# n2k-breakout-3_0-ISO.net
KiCad netlist of a schematic drawn in EAGLE
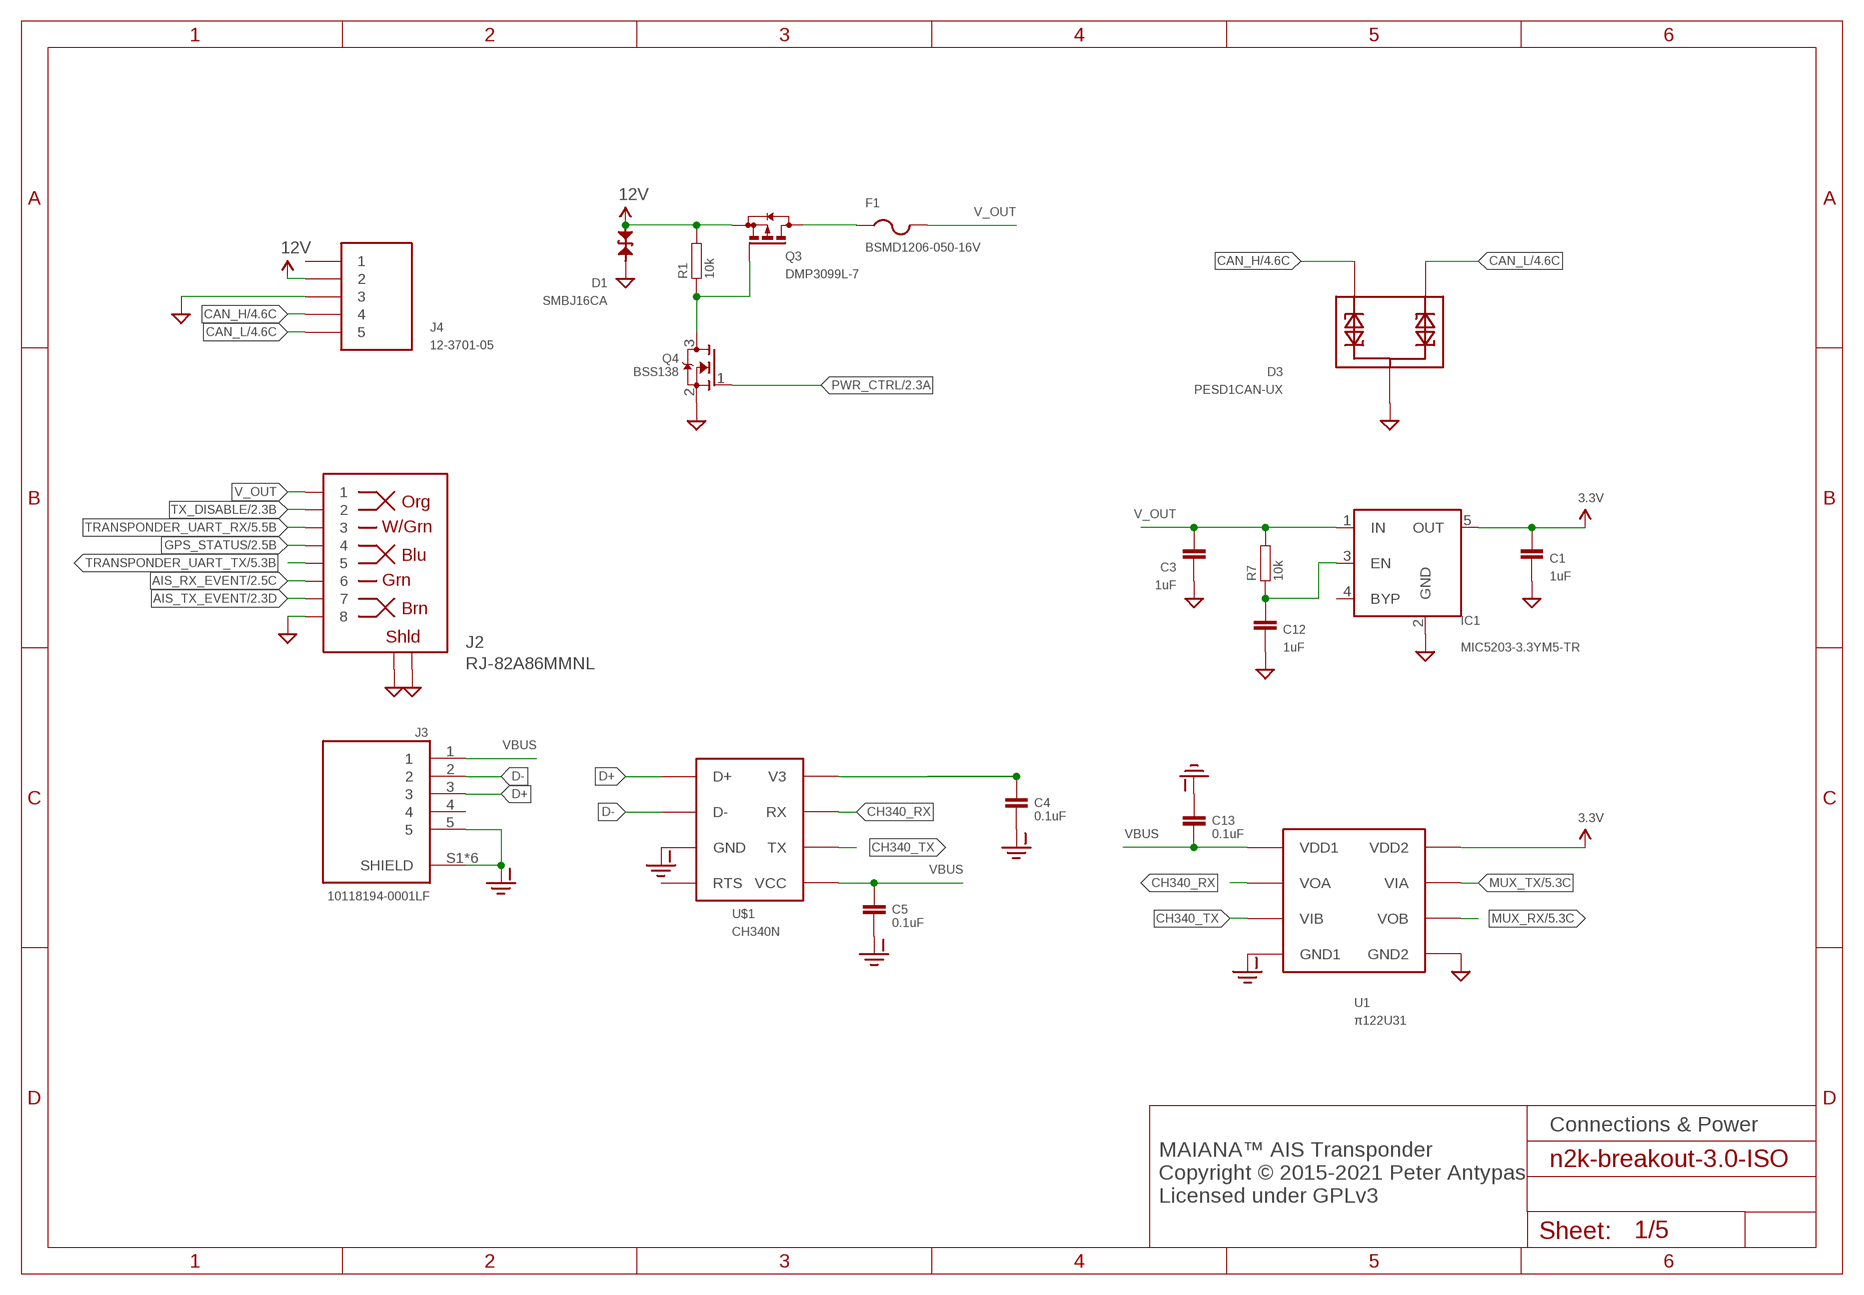
[diagram p0: schematic, sheet 1]
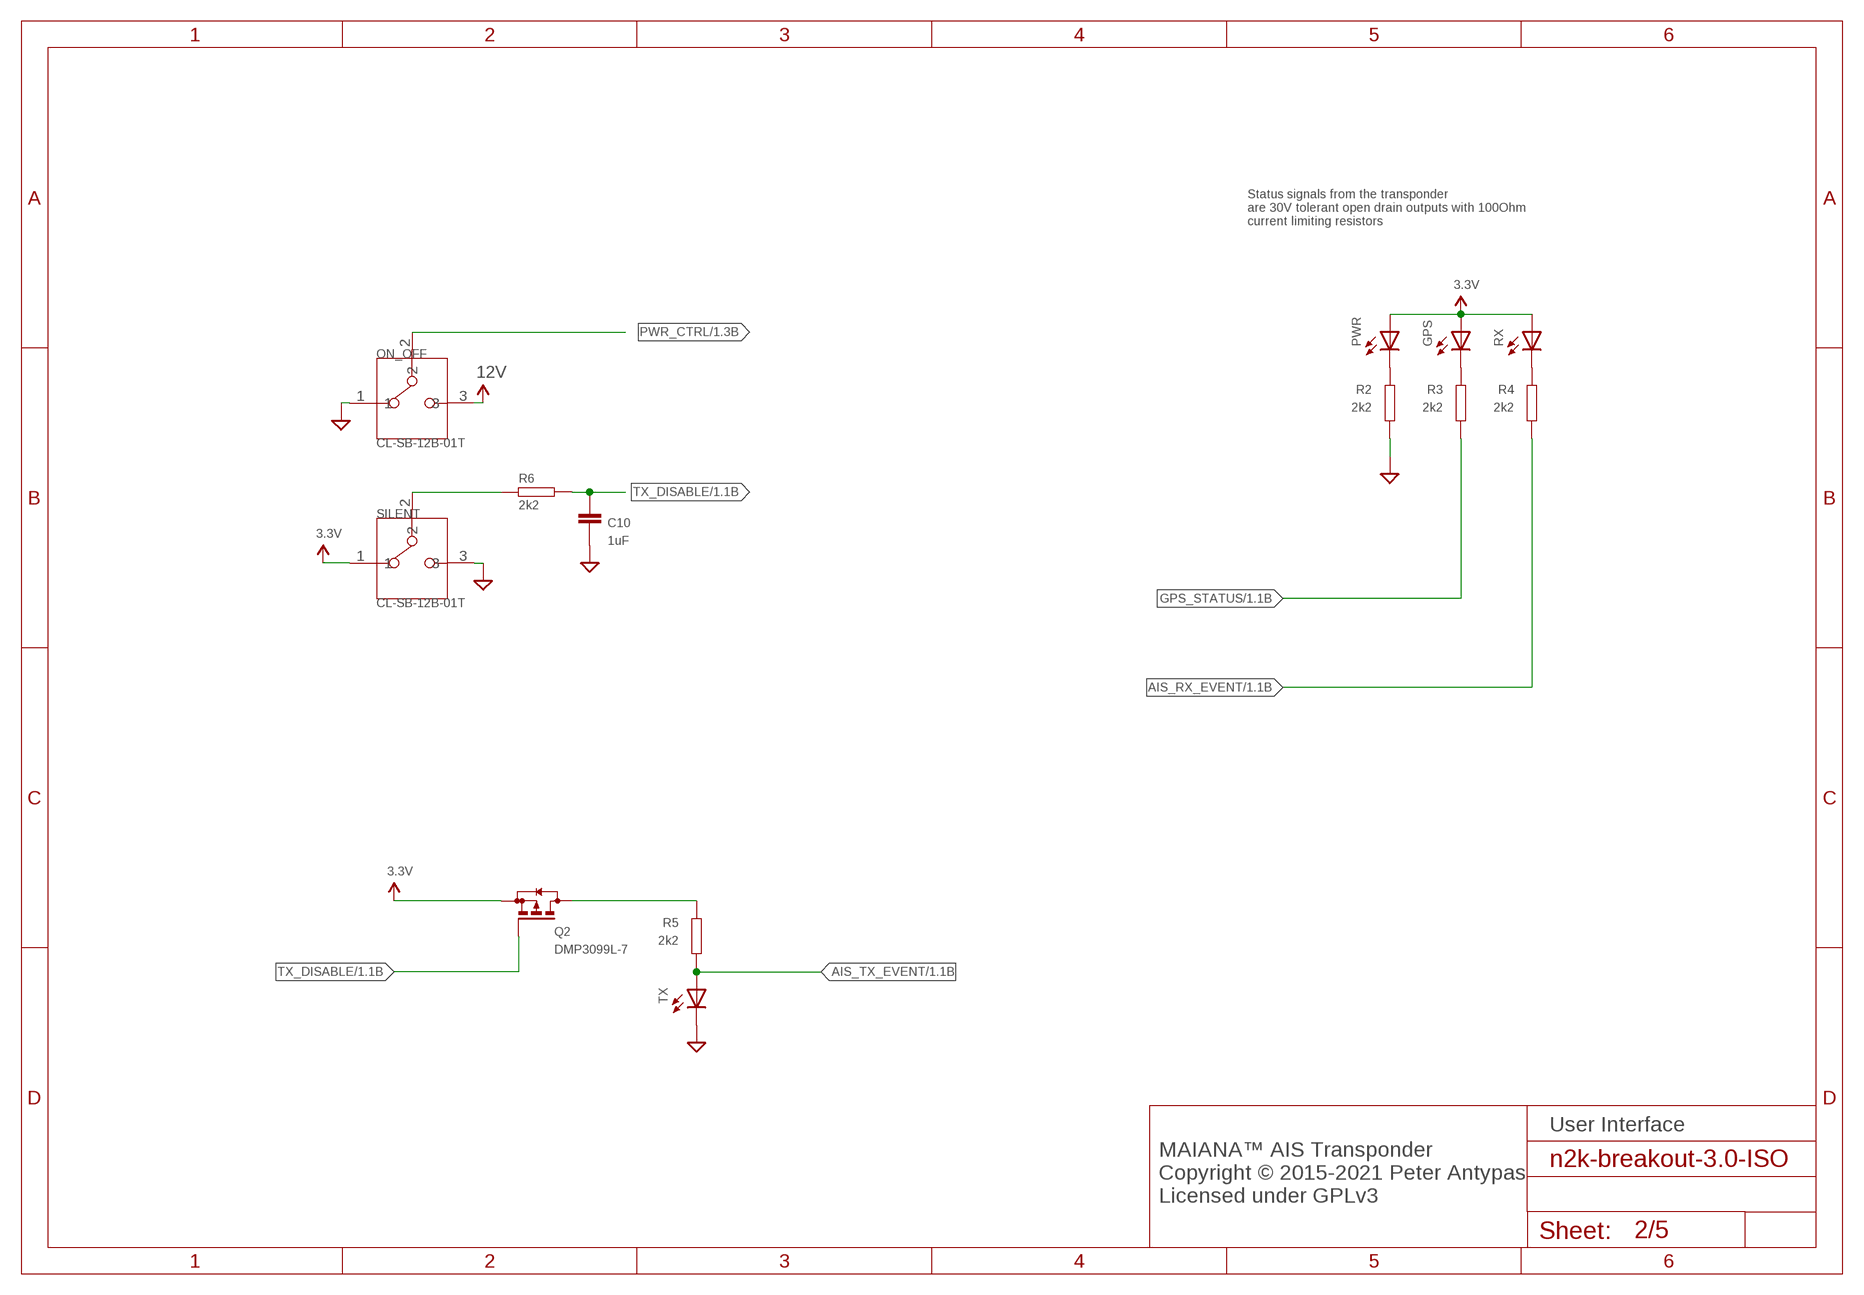
[diagram p1: schematic, sheet 2]
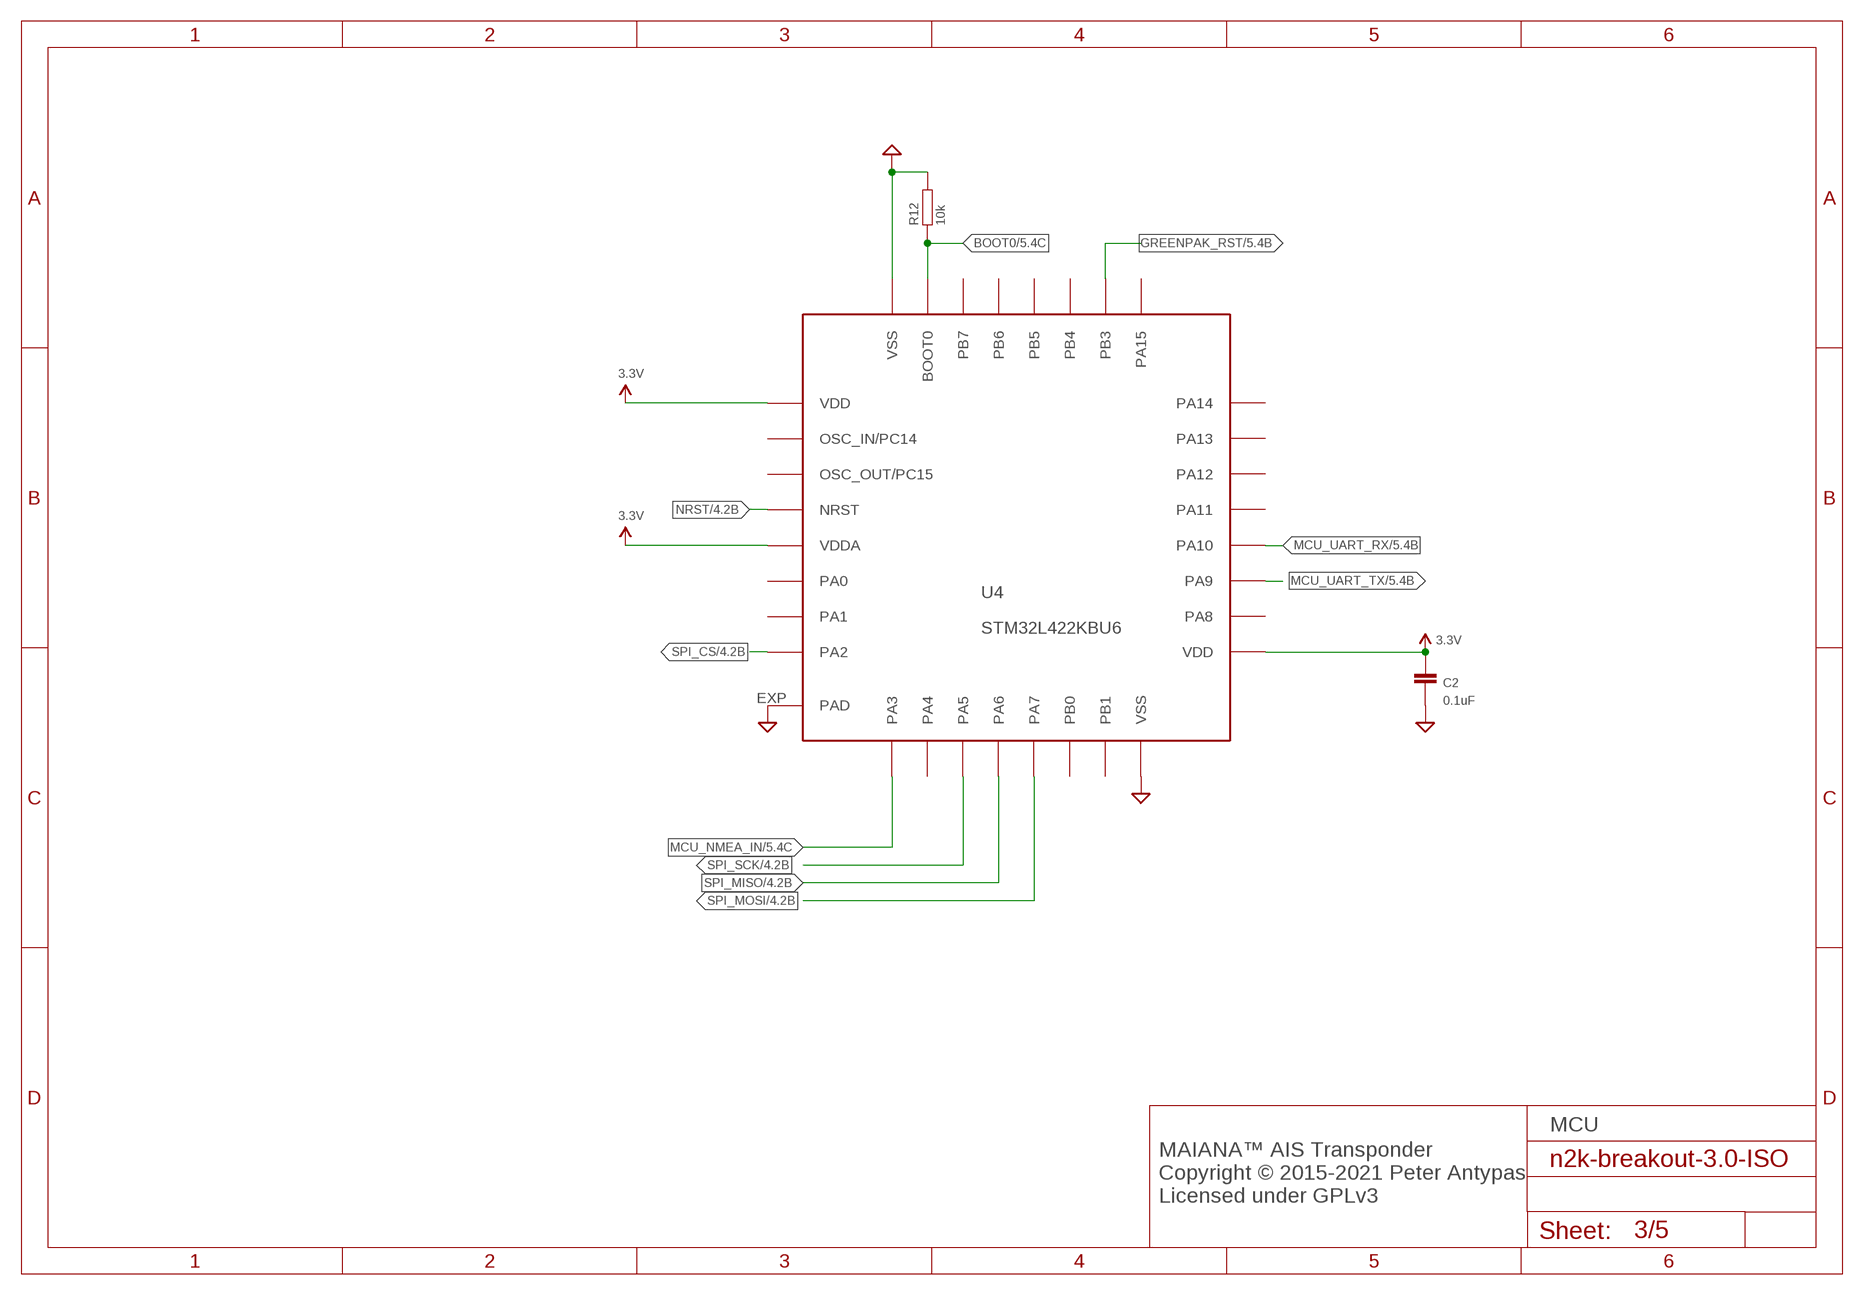
[diagram p2: schematic, sheet 3]
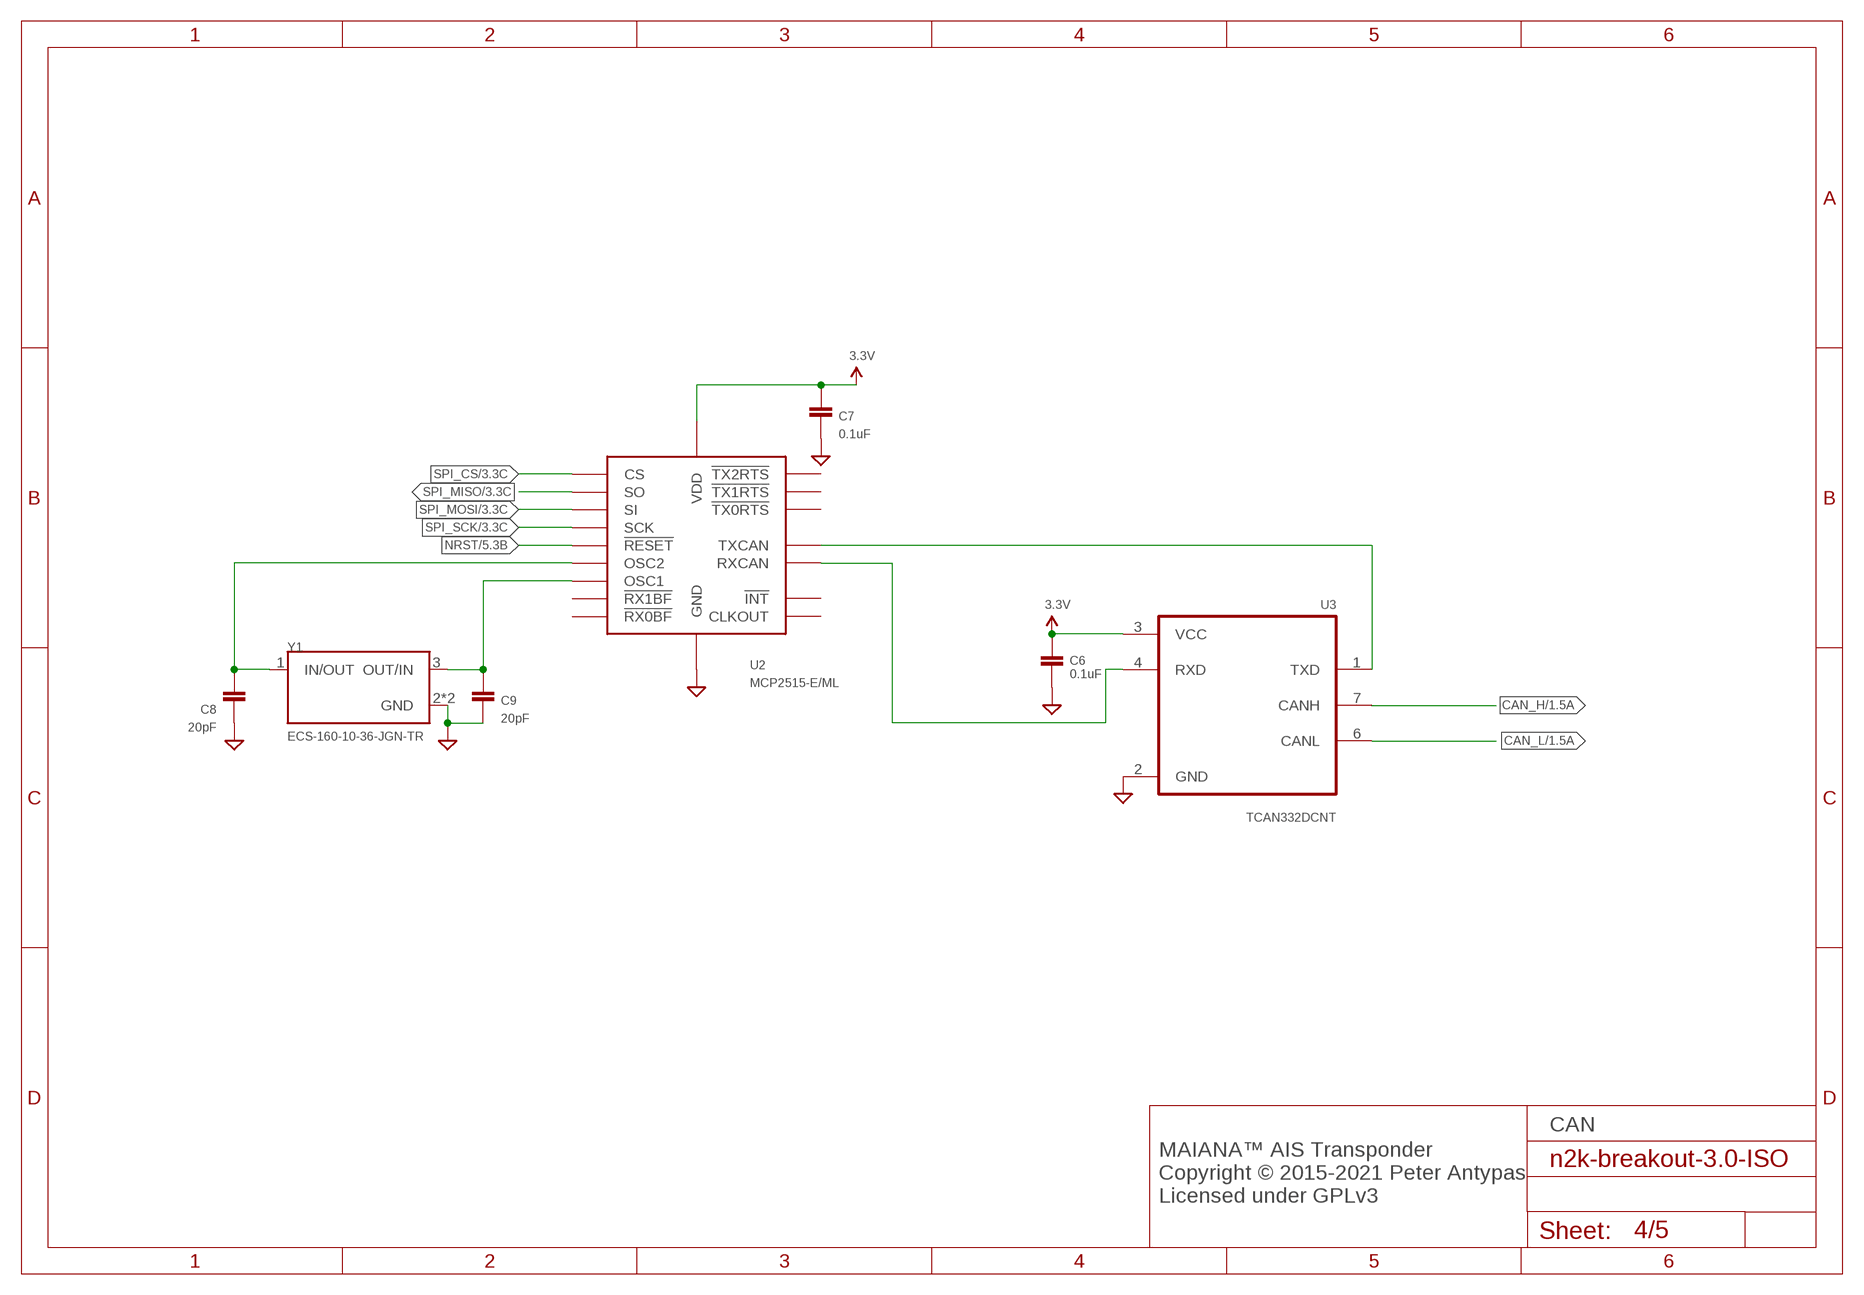
[diagram p3: schematic, sheet 4]
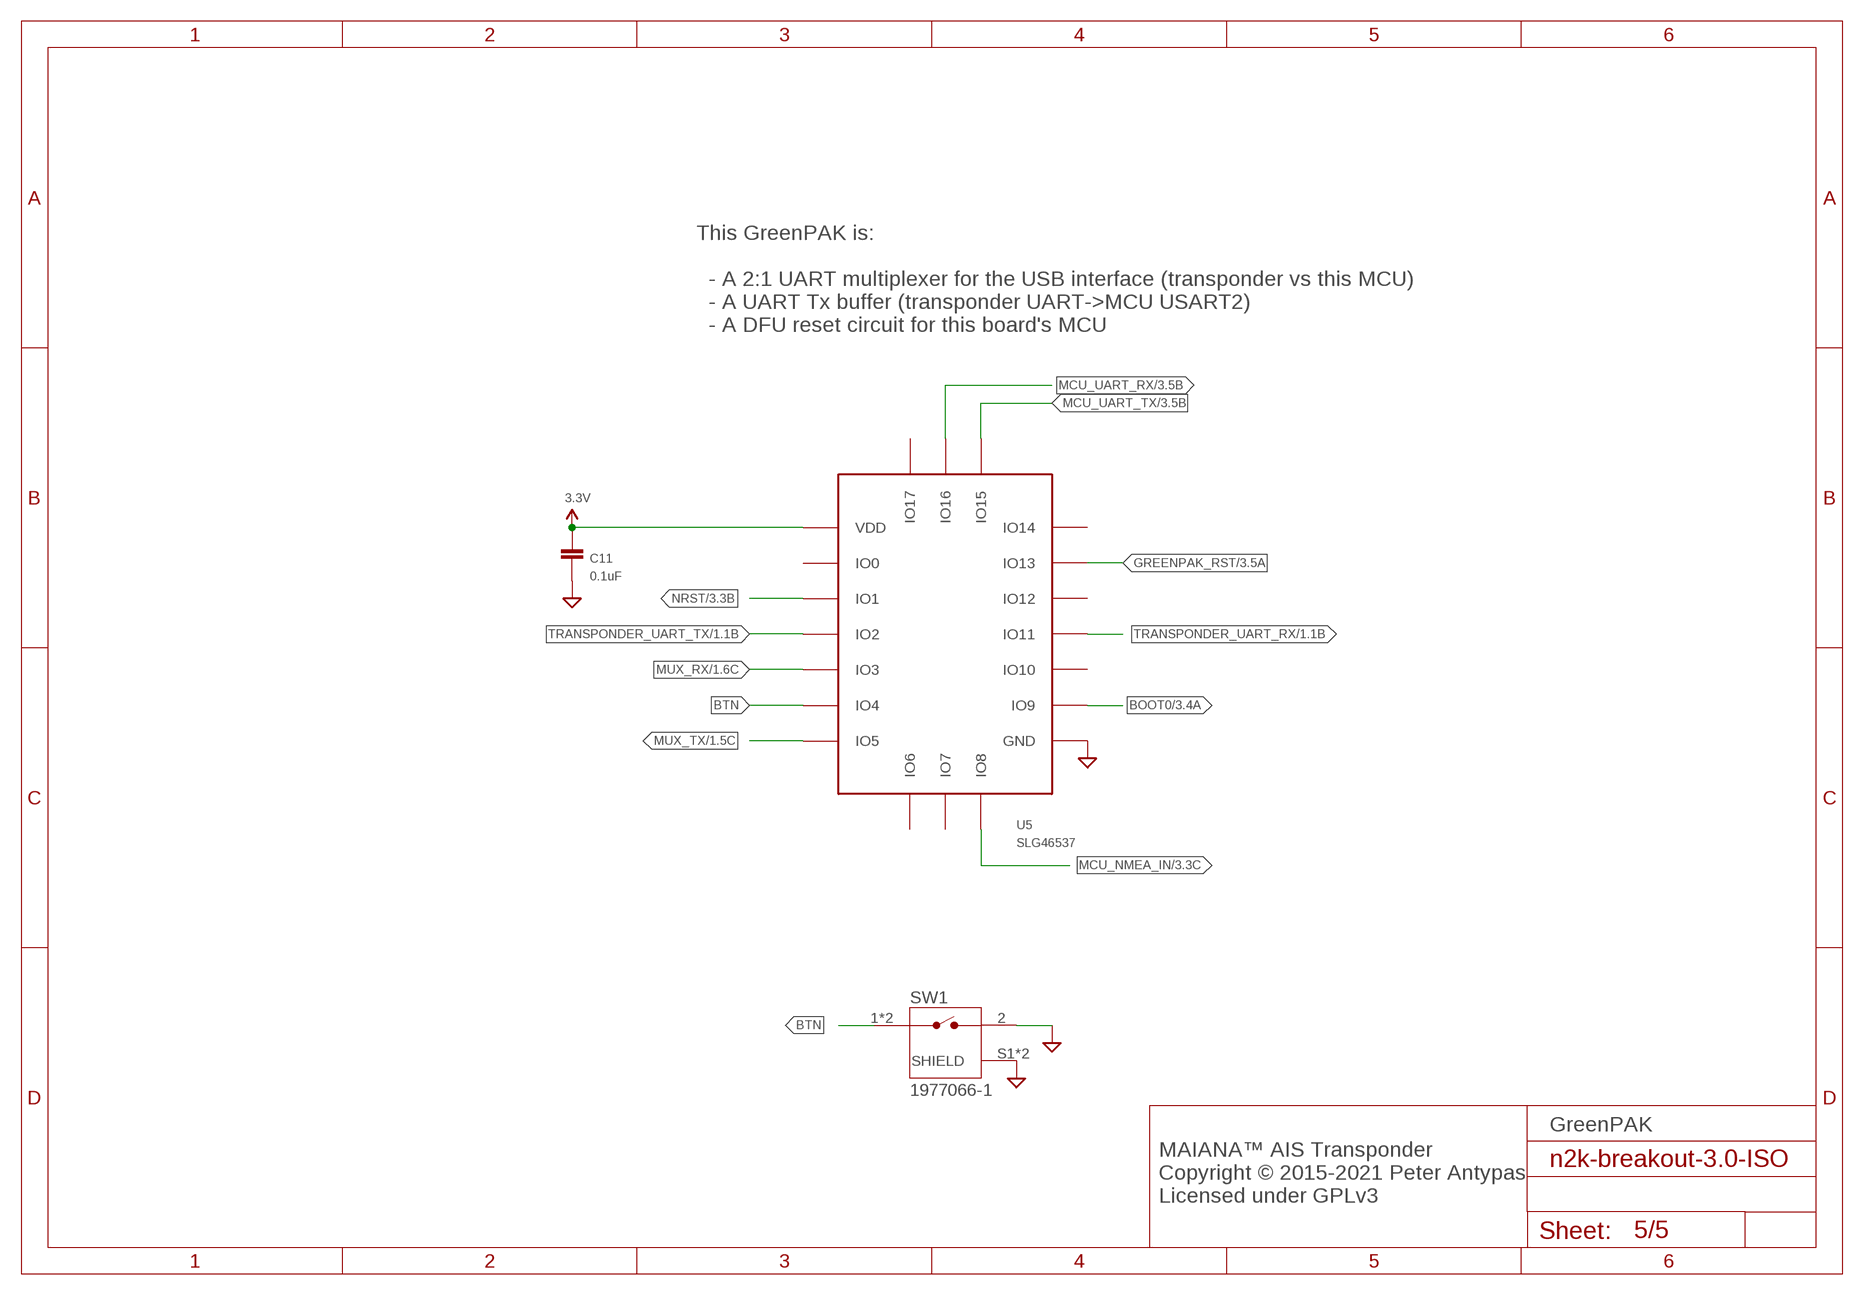
[diagram p4: schematic, sheet 5]

(export (version "E")
  (design (tool "Eeschema 10.0.6"))
  (components
    (comp (ref "C10")
      (value "1uF")
      (footprint "eagle-import:0603")
      (libsource (lib "eagle-import") (part "CAPACITOR0603"))
    )
    (comp (ref "GPS")
      (value "LEDCHIPLED_1206")
      (footprint "eagle-import:CHIPLED_1206")
      (fields (field (name "PARTNO") "TJ-S3216CL9T5ALC2G-A5"))
      (libsource (lib "eagle-import") (part "LEDCHIPLED_1206"))
    )
    (comp (ref "ON_OFF")
      (value "CL-SB-12B-01T")
      (footprint "eagle-import:CL-SB-12B")
      (fields (field (name "MF") "Nidec Copal"))
      (libsource (lib "eagle-import") (part "CL-SB-12B-01T"))
    )
    (comp (ref "PWR")
      (value "LEDCHIPLED_1206")
      (footprint "eagle-import:CHIPLED_1206")
      (fields (field (name "PARTNO") "TJ-S3216CL9T5ALC2G-A5"))
      (libsource (lib "eagle-import") (part "LEDCHIPLED_1206"))
    )
    (comp (ref "Q2")
      (value "DMP3099L-7")
      (footprint "eagle-import:SOT23")
      (libsource (lib "eagle-import") (part "BSS84"))
    )
    (comp (ref "R2")
      (value "2k2")
      (footprint "eagle-import:0603")
      (libsource (lib "eagle-import") (part "RESISTOR0603"))
    )
    (comp (ref "R3")
      (value "2k2")
      (footprint "eagle-import:0603")
      (libsource (lib "eagle-import") (part "RESISTOR0603"))
    )
    (comp (ref "R4")
      (value "2k2")
      (footprint "eagle-import:0603")
      (libsource (lib "eagle-import") (part "RESISTOR0603"))
    )
    (comp (ref "R5")
      (value "2k2")
      (footprint "eagle-import:0603")
      (libsource (lib "eagle-import") (part "RESISTOR0603"))
    )
    (comp (ref "R6")
      (value "2k2")
      (footprint "eagle-import:0603")
      (libsource (lib "eagle-import") (part "RESISTOR0603"))
    )
    (comp (ref "RX")
      (value "LEDCHIPLED_1206")
      (footprint "eagle-import:CHIPLED_1206")
      (fields (field (name "PARTNO") "TJ-S3216CL9T5ALC2G-A5"))
      (libsource (lib "eagle-import") (part "LEDCHIPLED_1206"))
    )
    (comp (ref "SILENT")
      (value "CL-SB-12B-01T")
      (footprint "eagle-import:CL-SB-12B")
      (fields (field (name "MF") "Nidec Copal"))
      (libsource (lib "eagle-import") (part "CL-SB-12B-01T"))
    )
    (comp (ref "TX")
      (value "LEDCHIPLED_1206")
      (footprint "eagle-import:CHIPLED_1206")
      (fields (field (name "PARTNO") "TJ-S3216CL9T5ALC2G-A5"))
      (libsource (lib "eagle-import") (part "LEDCHIPLED_1206"))
    )
    (comp (ref "C2")
      (value "0.1uF")
      (footprint "eagle-import:0603")
      (libsource (lib "eagle-import") (part "CAPACITOR0603"))
    )
    (comp (ref "R12")
      (value "10k")
      (footprint "eagle-import:0603")
      (libsource (lib "eagle-import") (part "RESISTOR0603"))
    )
    (comp (ref "U4")
      (value "STM32L422KBU6")
      (footprint "eagle-import:QFN32")
      (libsource (lib "eagle-import") (part "STM32L432KXXX"))
    )
    (comp (ref "C6")
      (value "0.1uF")
      (footprint "eagle-import:0603")
      (libsource (lib "eagle-import") (part "CAPACITOR0603"))
    )
    (comp (ref "C7")
      (value "0.1uF")
      (footprint "eagle-import:0603")
      (libsource (lib "eagle-import") (part "CAPACITOR0603"))
    )
    (comp (ref "C8")
      (value "20pF")
      (footprint "eagle-import:0603")
      (libsource (lib "eagle-import") (part "CAPACITOR0603"))
    )
    (comp (ref "C9")
      (value "20pF")
      (footprint "eagle-import:0603")
      (libsource (lib "eagle-import") (part "CAPACITOR0603"))
    )
    (comp (ref "U2")
      (value "MCP2515-E/ML")
      (footprint "eagle-import:QFN20-4X4")
      (libsource (lib "eagle-import") (part "MCP2515-QFN20"))
    )
    (comp (ref "U3")
      (value "TCAN332DCNT")
      (footprint "eagle-import:SOT65P280X145-8N")
      (fields (field (name "MF") "Texas Instruments") (field (name "MP") "TCAN332GDCNR"))
      (libsource (lib "eagle-import") (part "TCAN332GDCNR"))
    )
    (comp (ref "Y1")
      (value "ECS-160-10-36-JGN-TR")
      (footprint "eagle-import:XTAL_ECS-160-10-36-JGN-TR")
      (fields (field (name "MF") "ECS Inc.") (field (name "MP") "ECS-300-8-36CKM-TR"))
      (libsource (lib "eagle-import") (part "ECS-300-8-36CKM-TR"))
    )
    (comp (ref "C11")
      (value "0.1uF")
      (footprint "eagle-import:0603")
      (libsource (lib "eagle-import") (part "CAPACITOR0603"))
    )
    (comp (ref "SW1")
      (value "1977066-1")
      (footprint "eagle-import:TE_1977066-1")
      (fields (field (name "MF") "TE Connectivity"))
      (libsource (lib "eagle-import") (part "1977066-1"))
    )
    (comp (ref "U5")
      (value "SLG46537")
      (footprint "eagle-import:STQFN20L")
      (libsource (lib "eagle-import") (part "SLG46537"))
    )
    (comp (ref "C1")
      (value "1uF")
      (footprint "eagle-import:0603")
      (libsource (lib "eagle-import") (part "CAPACITOR0603"))
    )
    (comp (ref "C3")
      (value "1uF")
      (footprint "eagle-import:0603")
      (libsource (lib "eagle-import") (part "CAPACITOR0603"))
    )
    (comp (ref "C4")
      (value "0.1uF")
      (footprint "eagle-import:0603")
      (libsource (lib "eagle-import") (part "CAPACITOR0603"))
    )
    (comp (ref "C5")
      (value "0.1uF")
      (footprint "eagle-import:0603")
      (libsource (lib "eagle-import") (part "CAPACITOR0603"))
    )
    (comp (ref "C12")
      (value "1uF")
      (footprint "eagle-import:0603")
      (libsource (lib "eagle-import") (part "CAPACITOR0603"))
    )
    (comp (ref "C13")
      (value "0.1uF")
      (footprint "eagle-import:0603")
      (libsource (lib "eagle-import") (part "CAPACITOR0603"))
    )
    (comp (ref "D1")
      (value "SMBJ16CA")
      (footprint "eagle-import:SMB-BIDIR")
      (libsource (lib "eagle-import") (part "DIODE-TVS-BIDIRSMB"))
    )
    (comp (ref "D3")
      (value "PESD1CAN-UX")
      (footprint "eagle-import:SOT65P210X110-3N")
      (libsource (lib "eagle-import") (part "PESD1CAN-UX"))
    )
    (comp (ref "F1")
      (value "BSMD1206-050-16V")
      (footprint "eagle-import:R1206")
      (libsource (lib "eagle-import") (part "PTCFUSE-1206"))
    )
    (comp (ref "IC1")
      (value "MIC5203-3.3YM5-TR")
      (footprint "eagle-import:SOT23-5")
      (libsource (lib "eagle-import") (part "MIC5219XX"))
    )
    (comp (ref "J2")
      (value "RJ-82A86MMNL")
      (footprint "eagle-import:RJ-82A86MMNL")
      (libsource (lib "eagle-import") (part "RJ-82A86MMNL"))
    )
    (comp (ref "J3")
      (value "10118194-0001LF")
      (footprint "eagle-import:AMPHENOL_10118194-0001LF")
      (fields (field (name "MF") "Amphenol ICC (FCI)"))
      (libsource (lib "eagle-import") (part "10118194-0001LF"))
    )
    (comp (ref "J4")
      (value "12-3701-05")
      (footprint "eagle-import:MICRO_C_5PIN")
      (libsource (lib "eagle-import") (part "12-3701-05"))
    )
    (comp (ref "Q3")
      (value "DMP3099L-7")
      (footprint "eagle-import:SOT23")
      (libsource (lib "eagle-import") (part "BSS84"))
    )
    (comp (ref "Q4")
      (value "BSS138")
      (footprint "eagle-import:SOT23")
      (libsource (lib "eagle-import") (part "MOSFET-NREFLOW"))
    )
    (comp (ref "R1")
      (value "10k")
      (footprint "eagle-import:0603")
      (libsource (lib "eagle-import") (part "RESISTOR0603"))
    )
    (comp (ref "R7")
      (value "10k")
      (footprint "eagle-import:0603")
      (libsource (lib "eagle-import") (part "RESISTOR0603"))
    )
    (comp (ref "U$1")
      (value "CH340N")
      (footprint "eagle-import:SOIC-8")
      (libsource (lib "eagle-import") (part "CH330N"))
    )
    (comp (ref "U1")
      (value "π122U31")
      (footprint "eagle-import:SOIC8")
      (libsource (lib "eagle-import") (part "PI122U3X"))
    )
  )
  (nets
    (net (code "1") (name "3.3V") (class "Default")
      (node (ref "C1") (pin "P$1") (pinfunction "1_P$1") (pintype "passive"))
      (node (ref "C11") (pin "P$1") (pinfunction "1_P$1") (pintype "passive"))
      (node (ref "C2") (pin "P$1") (pinfunction "1_P$1") (pintype "passive"))
      (node (ref "C6") (pin "P$1") (pinfunction "1_P$1") (pintype "passive"))
      (node (ref "C7") (pin "P$1") (pinfunction "1_P$1") (pintype "passive"))
      (node (ref "GPS") (pin "A") (pinfunction "A_A") (pintype "passive"))
      (node (ref "IC1") (pin "5") (pinfunction "OUT_5") (pintype "output"))
      (node (ref "PWR") (pin "A") (pinfunction "A_A") (pintype "passive"))
      (node (ref "Q2") (pin "2") (pinfunction "S_2") (pintype "passive"))
      (node (ref "RX") (pin "A") (pinfunction "A_A") (pintype "passive"))
      (node (ref "SILENT") (pin "1") (pinfunction "1_1") (pintype "bidirectional"))
      (node (ref "U1") (pin "8") (pinfunction "VDD2_8") (pintype "bidirectional"))
      (node (ref "U2") (pin "18") (pinfunction "VDD_18") (pintype "bidirectional"))
      (node (ref "U3") (pin "3") (pinfunction "VCC_3") (pintype "power_in"))
      (node (ref "U4") (pin "1") (pinfunction "VDD_1") (pintype "bidirectional"))
      (node (ref "U4") (pin "17") (pinfunction "VDD_17") (pintype "bidirectional"))
      (node (ref "U4") (pin "5") (pinfunction "VDDA_5") (pintype "bidirectional"))
      (node (ref "U5") (pin "P$1") (pinfunction "VDD_P$1") (pintype "bidirectional"))
    )
    (net (code "2") (name "12V") (class "Default")
      (node (ref "D1") (pin "A") (pinfunction "P$1_A") (pintype "bidirectional"))
      (node (ref "J4") (pin "2") (pinfunction "2_2") (pintype "bidirectional"))
      (node (ref "ON_OFF") (pin "3") (pinfunction "3_3") (pintype "bidirectional"))
      (node (ref "Q3") (pin "2") (pinfunction "S_2") (pintype "passive"))
      (node (ref "R1") (pin "P$2") (pinfunction "P$2_P$2") (pintype "passive"))
    )
    (net (code "3") (name "AIS_RX_EVENT") (class "Default")
      (node (ref "J2") (pin "P$6") (pinfunction "6_P$6") (pintype "bidirectional"))
      (node (ref "R4") (pin "P$2") (pinfunction "P$2_P$2") (pintype "passive"))
    )
    (net (code "4") (name "AIS_TX_EVENT") (class "Default")
      (node (ref "J2") (pin "P$7") (pinfunction "7_P$7") (pintype "bidirectional"))
      (node (ref "R5") (pin "P$2") (pinfunction "P$2_P$2") (pintype "passive"))
      (node (ref "TX") (pin "A") (pinfunction "A_A") (pintype "passive"))
    )
    (net (code "5") (name "BOOT0") (class "Default")
      (node (ref "R12") (pin "P$1") (pinfunction "P$1_P$1") (pintype "passive"))
      (node (ref "U4") (pin "31") (pinfunction "BOOT0_31") (pintype "bidirectional"))
      (node (ref "U5") (pin "P$12") (pinfunction "IO9_P$12") (pintype "bidirectional"))
    )
    (net (code "6") (name "BTN") (class "Default")
      (node (ref "SW1") (pin "1") (pinfunction "1_1") (pintype "passive"))
      (node (ref "SW1") (pin "3") (pinfunction "1_3") (pintype "passive"))
      (node (ref "U5") (pin "P$6") (pinfunction "IO4_P$6") (pintype "bidirectional"))
    )
    (net (code "7") (name "CAN_H") (class "Default")
      (node (ref "D3") (pin "2") (pinfunction "P$2_2") (pintype "bidirectional"))
      (node (ref "J4") (pin "4") (pinfunction "4_4") (pintype "bidirectional"))
      (node (ref "U3") (pin "7") (pinfunction "CANH_7") (pintype "bidirectional"))
    )
    (net (code "8") (name "CAN_L") (class "Default")
      (node (ref "D3") (pin "1") (pinfunction "P$1_1") (pintype "bidirectional"))
      (node (ref "J4") (pin "5") (pinfunction "5_5") (pintype "bidirectional"))
      (node (ref "U3") (pin "6") (pinfunction "CANL_6") (pintype "bidirectional"))
    )
    (net (code "9") (name "CH340_RX") (class "Default")
      (node (ref "U$1") (pin "7") (pinfunction "RX_7") (pintype "bidirectional"))
      (node (ref "U1") (pin "2") (pinfunction "VOA_2") (pintype "bidirectional"))
    )
    (net (code "10") (name "CH340_TX") (class "Default")
      (node (ref "U$1") (pin "6") (pinfunction "TX_6") (pintype "bidirectional"))
      (node (ref "U1") (pin "3") (pinfunction "VIB_3") (pintype "bidirectional"))
    )
    (net (code "11") (name "D+") (class "Default")
      (node (ref "J3") (pin "3") (pinfunction "3_3") (pintype "passive"))
      (node (ref "U$1") (pin "1") (pinfunction "D+_1") (pintype "bidirectional"))
    )
    (net (code "12") (name "D-") (class "Default")
      (node (ref "J3") (pin "2") (pinfunction "2_2") (pintype "passive"))
      (node (ref "U$1") (pin "2") (pinfunction "D-_2") (pintype "bidirectional"))
    )
    (net (code "13") (name "GND") (class "Default")
      (node (ref "C1") (pin "P$2") (pinfunction "2_P$2") (pintype "passive"))
      (node (ref "C10") (pin "P$2") (pinfunction "2_P$2") (pintype "passive"))
      (node (ref "C11") (pin "P$2") (pinfunction "2_P$2") (pintype "passive"))
      (node (ref "C12") (pin "P$2") (pinfunction "2_P$2") (pintype "passive"))
      (node (ref "C2") (pin "P$2") (pinfunction "2_P$2") (pintype "passive"))
      (node (ref "C3") (pin "P$2") (pinfunction "2_P$2") (pintype "passive"))
      (node (ref "C6") (pin "P$2") (pinfunction "2_P$2") (pintype "passive"))
      (node (ref "C7") (pin "P$2") (pinfunction "2_P$2") (pintype "passive"))
      (node (ref "C8") (pin "P$2") (pinfunction "2_P$2") (pintype "passive"))
      (node (ref "C9") (pin "P$2") (pinfunction "2_P$2") (pintype "passive"))
      (node (ref "D1") (pin "C") (pinfunction "P$2_C") (pintype "bidirectional"))
      (node (ref "D3") (pin "3") (pinfunction "P$3_3") (pintype "bidirectional"))
      (node (ref "IC1") (pin "2") (pinfunction "GND_2") (pintype "power_in"))
      (node (ref "J2") (pin "P$10") (pinfunction "SHLD_P$10") (pintype "bidirectional"))
      (node (ref "J2") (pin "P$11") (pinfunction "SHLD_P$11") (pintype "bidirectional"))
      (node (ref "J2") (pin "P$12") (pinfunction "SHLD_P$12") (pintype "bidirectional"))
      (node (ref "J2") (pin "P$8") (pinfunction "8_P$8") (pintype "bidirectional"))
      (node (ref "J2") (pin "P$9") (pinfunction "SHLD_P$9") (pintype "bidirectional"))
      (node (ref "J4") (pin "3") (pinfunction "3_3") (pintype "bidirectional"))
      (node (ref "ON_OFF") (pin "1") (pinfunction "1_1") (pintype "bidirectional"))
      (node (ref "Q4") (pin "2") (pinfunction "S_2") (pintype "bidirectional"))
      (node (ref "R12") (pin "P$2") (pinfunction "P$2_P$2") (pintype "passive"))
      (node (ref "R2") (pin "P$2") (pinfunction "P$2_P$2") (pintype "passive"))
      (node (ref "SILENT") (pin "3") (pinfunction "3_3") (pintype "bidirectional"))
      (node (ref "SW1") (pin "2") (pinfunction "2_2") (pintype "passive"))
      (node (ref "SW1") (pin "S1") (pinfunction "SHIELD_S1") (pintype "passive"))
      (node (ref "SW1") (pin "S2") (pinfunction "SHIELD_S2") (pintype "passive"))
      (node (ref "TX") (pin "C") (pinfunction "C_C") (pintype "passive"))
      (node (ref "U1") (pin "5") (pinfunction "GND2_5") (pintype "bidirectional"))
      (node (ref "U2") (pin "8") (pinfunction "GND_8") (pintype "bidirectional"))
      (node (ref "U2") (pin "EXP") (pinfunction "GND_EXP") (pintype "bidirectional"))
      (node (ref "U3") (pin "2") (pinfunction "GND_2") (pintype "power_in"))
      (node (ref "U4") (pin "16") (pinfunction "VSS_16") (pintype "bidirectional"))
      (node (ref "U4") (pin "32") (pinfunction "VSS_32") (pintype "bidirectional"))
      (node (ref "U4") (pin "EXP") (pinfunction "PAD_EXP") (pintype "bidirectional"))
      (node (ref "U5") (pin "P$11") (pinfunction "GND_P$11") (pintype "bidirectional"))
      (node (ref "Y1") (pin "2") (pinfunction "GND_2") (pintype "power_in"))
      (node (ref "Y1") (pin "4") (pinfunction "GND_4") (pintype "power_in"))
    )
    (net (code "14") (name "GND-ISO") (class "Default")
      (node (ref "C13") (pin "P$1") (pinfunction "1_P$1") (pintype "passive"))
      (node (ref "C4") (pin "P$2") (pinfunction "2_P$2") (pintype "passive"))
      (node (ref "C5") (pin "P$2") (pinfunction "2_P$2") (pintype "passive"))
      (node (ref "J3") (pin "5") (pinfunction "5_5") (pintype "passive"))
      (node (ref "J3") (pin "S1") (pinfunction "SHIELD_S1") (pintype "passive"))
      (node (ref "J3") (pin "S2") (pinfunction "SHIELD_S2") (pintype "passive"))
      (node (ref "J3") (pin "S3") (pinfunction "SHIELD_S3") (pintype "passive"))
      (node (ref "J3") (pin "S4") (pinfunction "SHIELD_S4") (pintype "passive"))
      (node (ref "J3") (pin "S5") (pinfunction "SHIELD_S5") (pintype "passive"))
      (node (ref "J3") (pin "S6") (pinfunction "SHIELD_S6") (pintype "passive"))
      (node (ref "U$1") (pin "3") (pinfunction "GND_3") (pintype "bidirectional"))
      (node (ref "U1") (pin "4") (pinfunction "GND1_4") (pintype "bidirectional"))
    )
    (net (code "15") (name "GPS_STATUS") (class "Default")
      (node (ref "J2") (pin "P$4") (pinfunction "4_P$4") (pintype "bidirectional"))
      (node (ref "R3") (pin "P$2") (pinfunction "P$2_P$2") (pintype "passive"))
    )
    (net (code "16") (name "GREENPAK_RST") (class "Default")
      (node (ref "U4") (pin "26") (pinfunction "PB3_26") (pintype "bidirectional"))
      (node (ref "U5") (pin "P$16") (pinfunction "IO13_P$16") (pintype "bidirectional"))
    )
    (net (code "17") (name "MCU_NMEA_IN") (class "Default")
      (node (ref "U4") (pin "9") (pinfunction "PA3_9") (pintype "bidirectional"))
      (node (ref "U5") (pin "P$10") (pinfunction "IO8_P$10") (pintype "bidirectional"))
    )
    (net (code "18") (name "MCU_UART_RX") (class "Default")
      (node (ref "U4") (pin "20") (pinfunction "PA10_20") (pintype "bidirectional"))
      (node (ref "U5") (pin "P$19") (pinfunction "IO16_P$19") (pintype "bidirectional"))
    )
    (net (code "19") (name "MCU_UART_TX") (class "Default")
      (node (ref "U4") (pin "19") (pinfunction "PA9_19") (pintype "bidirectional"))
      (node (ref "U5") (pin "P$18") (pinfunction "IO15_P$18") (pintype "bidirectional"))
    )
    (net (code "20") (name "MUX_RX") (class "Default")
      (node (ref "U1") (pin "6") (pinfunction "VOB_6") (pintype "bidirectional"))
      (node (ref "U5") (pin "P$5") (pinfunction "IO3_P$5") (pintype "bidirectional"))
    )
    (net (code "21") (name "MUX_TX") (class "Default")
      (node (ref "U1") (pin "7") (pinfunction "VIA_7") (pintype "bidirectional"))
      (node (ref "U5") (pin "P$7") (pinfunction "IO5_P$7") (pintype "bidirectional"))
    )
    (net (code "22") (name "NRST") (class "Default")
      (node (ref "U2") (pin "17") (pinfunction "~{RESET}_17") (pintype "bidirectional"))
      (node (ref "U4") (pin "4") (pinfunction "NRST_4") (pintype "bidirectional"))
      (node (ref "U5") (pin "P$3") (pinfunction "IO1_P$3") (pintype "bidirectional"))
    )
    (net (code "23") (name "Net-(C4-1)") (class "Default")
      (node (ref "C4") (pin "P$1") (pinfunction "1_P$1") (pintype "passive"))
      (node (ref "U$1") (pin "8") (pinfunction "V3_8") (pintype "bidirectional"))
    )
    (net (code "24") (name "Net-(C8-1)") (class "Default")
      (node (ref "C8") (pin "P$1") (pinfunction "1_P$1") (pintype "passive"))
      (node (ref "U2") (pin "6") (pinfunction "OSC2_6") (pintype "bidirectional"))
      (node (ref "Y1") (pin "1") (pinfunction "IN/OUT_1") (pintype "bidirectional"))
    )
    (net (code "25") (name "Net-(C9-1)") (class "Default")
      (node (ref "C9") (pin "P$1") (pinfunction "1_P$1") (pintype "passive"))
      (node (ref "U2") (pin "7") (pinfunction "OSC1_7") (pintype "bidirectional"))
      (node (ref "Y1") (pin "3") (pinfunction "OUT/IN_3") (pintype "bidirectional"))
    )
    (net (code "26") (name "Net-(C12-1)") (class "Default")
      (node (ref "C12") (pin "P$1") (pinfunction "1_P$1") (pintype "passive"))
      (node (ref "IC1") (pin "3") (pinfunction "EN_3") (pintype "input"))
      (node (ref "R7") (pin "P$1") (pinfunction "P$1_P$1") (pintype "passive"))
    )
    (net (code "27") (name "Net-(GPS-PadC)") (class "Default")
      (node (ref "GPS") (pin "C") (pinfunction "C_C") (pintype "passive"))
      (node (ref "R3") (pin "P$1") (pinfunction "P$1_P$1") (pintype "passive"))
    )
    (net (code "28") (name "Net-(PWR-PadC)") (class "Default")
      (node (ref "PWR") (pin "C") (pinfunction "C_C") (pintype "passive"))
      (node (ref "R2") (pin "P$1") (pinfunction "P$1_P$1") (pintype "passive"))
    )
    (net (code "29") (name "Net-(Q2-D)") (class "Default")
      (node (ref "Q2") (pin "3") (pinfunction "D_3") (pintype "passive"))
      (node (ref "R5") (pin "P$1") (pinfunction "P$1_P$1") (pintype "passive"))
    )
    (net (code "30") (name "Net-(Q3-D)") (class "Default")
      (node (ref "F1") (pin "1") (pinfunction "1_1") (pintype "passive"))
      (node (ref "Q3") (pin "3") (pinfunction "D_3") (pintype "passive"))
    )
    (net (code "31") (name "Net-(Q3-G)") (class "Default")
      (node (ref "Q3") (pin "1") (pinfunction "G_1") (pintype "passive"))
      (node (ref "Q4") (pin "3") (pinfunction "D_3") (pintype "bidirectional"))
      (node (ref "R1") (pin "P$1") (pinfunction "P$1_P$1") (pintype "passive"))
    )
    (net (code "32") (name "Net-(R4-PadP$1)") (class "Default")
      (node (ref "R4") (pin "P$1") (pinfunction "P$1_P$1") (pintype "passive"))
      (node (ref "RX") (pin "C") (pinfunction "C_C") (pintype "passive"))
    )
    (net (code "33") (name "Net-(R6-PadP$1)") (class "Default")
      (node (ref "R6") (pin "P$1") (pinfunction "P$1_P$1") (pintype "passive"))
      (node (ref "SILENT") (pin "2") (pinfunction "2_2") (pintype "bidirectional"))
    )
    (net (code "34") (name "Net-(U2-RXCAN)") (class "Default")
      (node (ref "U2") (pin "20") (pinfunction "RXCAN_20") (pintype "bidirectional"))
      (node (ref "U3") (pin "4") (pinfunction "RXD_4") (pintype "output"))
    )
    (net (code "35") (name "Net-(U2-TXCAN)") (class "Default")
      (node (ref "U2") (pin "19") (pinfunction "TXCAN_19") (pintype "bidirectional"))
      (node (ref "U3") (pin "1") (pinfunction "TXD_1") (pintype "input"))
    )
    (net (code "36") (name "PWR_CTRL") (class "Default")
      (node (ref "ON_OFF") (pin "2") (pinfunction "2_2") (pintype "bidirectional"))
      (node (ref "Q4") (pin "1") (pinfunction "G_1") (pintype "bidirectional"))
    )
    (net (code "37") (name "SPI_CS") (class "Default")
      (node (ref "U2") (pin "16") (pinfunction "CS_16") (pintype "bidirectional"))
      (node (ref "U4") (pin "8") (pinfunction "PA2_8") (pintype "bidirectional"))
    )
    (net (code "38") (name "SPI_MISO") (class "Default")
      (node (ref "U2") (pin "15") (pinfunction "SO_15") (pintype "bidirectional"))
      (node (ref "U4") (pin "12") (pinfunction "PA6_12") (pintype "bidirectional"))
    )
    (net (code "39") (name "SPI_MOSI") (class "Default")
      (node (ref "U2") (pin "14") (pinfunction "SI_14") (pintype "bidirectional"))
      (node (ref "U4") (pin "13") (pinfunction "PA7_13") (pintype "bidirectional"))
    )
    (net (code "40") (name "SPI_SCK") (class "Default")
      (node (ref "U2") (pin "12") (pinfunction "SCK_12") (pintype "bidirectional"))
      (node (ref "U4") (pin "11") (pinfunction "PA5_11") (pintype "bidirectional"))
    )
    (net (code "41") (name "TRANSPONDER_UART_RX") (class "Default")
      (node (ref "J2") (pin "P$3") (pinfunction "3_P$3") (pintype "bidirectional"))
      (node (ref "U5") (pin "P$14") (pinfunction "IO11_P$14") (pintype "bidirectional"))
    )
    (net (code "42") (name "TRANSPONDER_UART_TX") (class "Default")
      (node (ref "J2") (pin "P$5") (pinfunction "5_P$5") (pintype "bidirectional"))
      (node (ref "U5") (pin "P$4") (pinfunction "IO2_P$4") (pintype "bidirectional"))
    )
    (net (code "43") (name "TX_DISABLE") (class "Default")
      (node (ref "C10") (pin "P$1") (pinfunction "1_P$1") (pintype "passive"))
      (node (ref "J2") (pin "P$2") (pinfunction "2_P$2") (pintype "bidirectional"))
      (node (ref "Q2") (pin "1") (pinfunction "G_1") (pintype "passive"))
      (node (ref "R6") (pin "P$2") (pinfunction "P$2_P$2") (pintype "passive"))
    )
    (net (code "44") (name "VBUS") (class "Default")
      (node (ref "C13") (pin "P$2") (pinfunction "2_P$2") (pintype "passive"))
      (node (ref "C5") (pin "P$1") (pinfunction "1_P$1") (pintype "passive"))
      (node (ref "J3") (pin "1") (pinfunction "1_1") (pintype "passive"))
      (node (ref "U$1") (pin "5") (pinfunction "VCC_5") (pintype "bidirectional"))
      (node (ref "U1") (pin "1") (pinfunction "VDD1_1") (pintype "bidirectional"))
    )
    (net (code "45") (name "V_OUT") (class "Default")
      (node (ref "C3") (pin "P$1") (pinfunction "1_P$1") (pintype "passive"))
      (node (ref "F1") (pin "2") (pinfunction "2_2") (pintype "passive"))
      (node (ref "IC1") (pin "1") (pinfunction "IN_1") (pintype "input"))
      (node (ref "J2") (pin "P$1") (pinfunction "1_P$1") (pintype "bidirectional"))
      (node (ref "R7") (pin "P$2") (pinfunction "P$2_P$2") (pintype "passive"))
    )
    (net (code "46") (name "unconnected-(IC1-BYP-Pad4)") (class "Default")
      (node (ref "IC1") (pin "4") (pinfunction "BYP_4") (pintype "passive"))
    )
    (net (code "47") (name "unconnected-(J3-Pad4)") (class "Default")
      (node (ref "J3") (pin "4") (pinfunction "4_4") (pintype "passive"))
    )
    (net (code "48") (name "unconnected-(J4-Pad1)") (class "Default")
      (node (ref "J4") (pin "1") (pinfunction "1_1") (pintype "bidirectional"))
    )
    (net (code "49") (name "unconnected-(U$1-RTS-Pad4)") (class "Default")
      (node (ref "U$1") (pin "4") (pinfunction "RTS_4") (pintype "bidirectional"))
    )
    (net (code "50") (name "unconnected-(U2-CLKOUT-Pad1)") (class "Default")
      (node (ref "U2") (pin "1") (pinfunction "CLKOUT_1") (pintype "bidirectional"))
    )
    (net (code "51") (name "unconnected-(U2-~{INT}-Pad11)") (class "Default")
      (node (ref "U2") (pin "11") (pinfunction "~{INT}_11") (pintype "bidirectional"))
    )
    (net (code "52") (name "unconnected-(U2-~{RX0BF}-Pad10)") (class "Default")
      (node (ref "U2") (pin "10") (pinfunction "~{RX0BF}_10") (pintype "bidirectional"))
    )
    (net (code "53") (name "unconnected-(U2-~{RX1BF}-Pad9)") (class "Default")
      (node (ref "U2") (pin "9") (pinfunction "~{RX1BF}_9") (pintype "bidirectional"))
    )
    (net (code "54") (name "unconnected-(U2-~{TX0RTS}-Pad2)") (class "Default")
      (node (ref "U2") (pin "2") (pinfunction "~{TX0RTS}_2") (pintype "bidirectional"))
    )
    (net (code "55") (name "unconnected-(U2-~{TX1RTS}-Pad3)") (class "Default")
      (node (ref "U2") (pin "3") (pinfunction "~{TX1RTS}_3") (pintype "bidirectional"))
    )
    (net (code "56") (name "unconnected-(U2-~{TX2RTS}-Pad5)") (class "Default")
      (node (ref "U2") (pin "5") (pinfunction "~{TX2RTS}_5") (pintype "bidirectional"))
    )
    (net (code "57") (name "unconnected-(U4-OSC_IN{slash}PC14-Pad2)") (class "Default")
      (node (ref "U4") (pin "2") (pinfunction "OSC_IN/PC14_2") (pintype "bidirectional"))
    )
    (net (code "58") (name "unconnected-(U4-OSC_OUT{slash}PC15-Pad3)") (class "Default")
      (node (ref "U4") (pin "3") (pinfunction "OSC_OUT/PC15_3") (pintype "bidirectional"))
    )
    (net (code "59") (name "unconnected-(U4-PA0-Pad6)") (class "Default")
      (node (ref "U4") (pin "6") (pinfunction "PA0_6") (pintype "bidirectional"))
    )
    (net (code "60") (name "unconnected-(U4-PA1-Pad7)") (class "Default")
      (node (ref "U4") (pin "7") (pinfunction "PA1_7") (pintype "bidirectional"))
    )
    (net (code "61") (name "unconnected-(U4-PA4-Pad10)") (class "Default")
      (node (ref "U4") (pin "10") (pinfunction "PA4_10") (pintype "bidirectional"))
    )
    (net (code "62") (name "unconnected-(U4-PA8-Pad18)") (class "Default")
      (node (ref "U4") (pin "18") (pinfunction "PA8_18") (pintype "bidirectional"))
    )
    (net (code "63") (name "unconnected-(U4-PA11-Pad21)") (class "Default")
      (node (ref "U4") (pin "21") (pinfunction "PA11_21") (pintype "bidirectional"))
    )
    (net (code "64") (name "unconnected-(U4-PA12-Pad22)") (class "Default")
      (node (ref "U4") (pin "22") (pinfunction "PA12_22") (pintype "bidirectional"))
    )
    (net (code "65") (name "unconnected-(U4-PA13-Pad23)") (class "Default")
      (node (ref "U4") (pin "23") (pinfunction "PA13_23") (pintype "bidirectional"))
    )
    (net (code "66") (name "unconnected-(U4-PA14-Pad24)") (class "Default")
      (node (ref "U4") (pin "24") (pinfunction "PA14_24") (pintype "bidirectional"))
    )
    (net (code "67") (name "unconnected-(U4-PA15-Pad25)") (class "Default")
      (node (ref "U4") (pin "25") (pinfunction "PA15_25") (pintype "bidirectional"))
    )
    (net (code "68") (name "unconnected-(U4-PB0-Pad14)") (class "Default")
      (node (ref "U4") (pin "14") (pinfunction "PB0_14") (pintype "bidirectional"))
    )
    (net (code "69") (name "unconnected-(U4-PB1-Pad15)") (class "Default")
      (node (ref "U4") (pin "15") (pinfunction "PB1_15") (pintype "bidirectional"))
    )
    (net (code "70") (name "unconnected-(U4-PB4-Pad27)") (class "Default")
      (node (ref "U4") (pin "27") (pinfunction "PB4_27") (pintype "bidirectional"))
    )
    (net (code "71") (name "unconnected-(U4-PB5-Pad28)") (class "Default")
      (node (ref "U4") (pin "28") (pinfunction "PB5_28") (pintype "bidirectional"))
    )
    (net (code "72") (name "unconnected-(U4-PB6-Pad29)") (class "Default")
      (node (ref "U4") (pin "29") (pinfunction "PB6_29") (pintype "bidirectional"))
    )
    (net (code "73") (name "unconnected-(U4-PB7-Pad30)") (class "Default")
      (node (ref "U4") (pin "30") (pinfunction "PB7_30") (pintype "bidirectional"))
    )
    (net (code "74") (name "unconnected-(U5-IO0-PadP$2)") (class "Default")
      (node (ref "U5") (pin "P$2") (pinfunction "IO0_P$2") (pintype "bidirectional"))
    )
    (net (code "75") (name "unconnected-(U5-IO6-PadP$8)") (class "Default")
      (node (ref "U5") (pin "P$8") (pinfunction "IO6_P$8") (pintype "bidirectional"))
    )
    (net (code "76") (name "unconnected-(U5-IO7-PadP$9)") (class "Default")
      (node (ref "U5") (pin "P$9") (pinfunction "IO7_P$9") (pintype "bidirectional"))
    )
    (net (code "77") (name "unconnected-(U5-IO10-PadP$13)") (class "Default")
      (node (ref "U5") (pin "P$13") (pinfunction "IO10_P$13") (pintype "bidirectional"))
    )
    (net (code "78") (name "unconnected-(U5-IO12-PadP$15)") (class "Default")
      (node (ref "U5") (pin "P$15") (pinfunction "IO12_P$15") (pintype "bidirectional"))
    )
    (net (code "79") (name "unconnected-(U5-IO14-PadP$17)") (class "Default")
      (node (ref "U5") (pin "P$17") (pinfunction "IO14_P$17") (pintype "bidirectional"))
    )
    (net (code "80") (name "unconnected-(U5-IO17-PadP$20)") (class "Default")
      (node (ref "U5") (pin "P$20") (pinfunction "IO17_P$20") (pintype "bidirectional"))
    )
  )
)
